# Power_Supply_Circuit_Manual.net
KiCad netlist of a schematic drawn in EAGLE
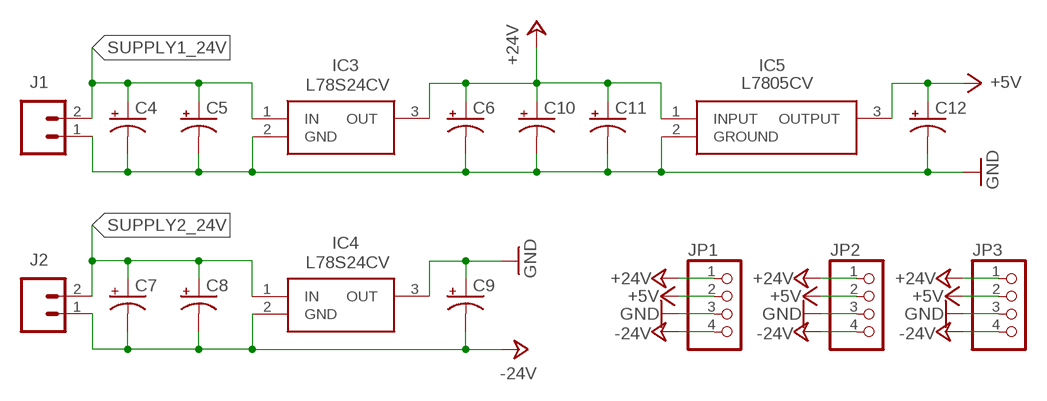
[diagram p0: schematic, sheet 1]

(export (version "E")
  (design (tool "Eeschema 10.0.6"))
  (components
    (comp (ref "C4")
      (value "CPOL-USE2.5-7")
      (footprint "eagle-import:E2,5-7")
      (libsource (lib "eagle-import") (part "CPOL-USE2.5-7"))
    )
    (comp (ref "C5")
      (value "CPOL-USE2.5-7")
      (footprint "eagle-import:E2,5-7")
      (libsource (lib "eagle-import") (part "CPOL-USE2.5-7"))
    )
    (comp (ref "C6")
      (value "CPOL-USE2.5-5")
      (footprint "eagle-import:E2,5-5")
      (libsource (lib "eagle-import") (part "CPOL-USE2.5-5"))
    )
    (comp (ref "C7")
      (value "CPOL-USE2.5-7")
      (footprint "eagle-import:E2,5-7")
      (libsource (lib "eagle-import") (part "CPOL-USE2.5-7"))
    )
    (comp (ref "C8")
      (value "CPOL-USE2.5-7")
      (footprint "eagle-import:E2,5-7")
      (libsource (lib "eagle-import") (part "CPOL-USE2.5-7"))
    )
    (comp (ref "C9")
      (value "CPOL-USE2.5-5")
      (footprint "eagle-import:E2,5-5")
      (libsource (lib "eagle-import") (part "CPOL-USE2.5-5"))
    )
    (comp (ref "C10")
      (value "CPOL-USE2.5-7")
      (footprint "eagle-import:E2,5-7")
      (libsource (lib "eagle-import") (part "CPOL-USE2.5-7"))
    )
    (comp (ref "C11")
      (value "CPOL-USE2.5-7")
      (footprint "eagle-import:E2,5-7")
      (libsource (lib "eagle-import") (part "CPOL-USE2.5-7"))
    )
    (comp (ref "C12")
      (value "CPOL-USE2.5-5")
      (footprint "eagle-import:E2,5-5")
      (libsource (lib "eagle-import") (part "CPOL-USE2.5-5"))
    )
    (comp (ref "IC3")
      (value "L78S24CV")
      (footprint "eagle-import:TO270P460X1020X2008-3P")
      (fields (field (name "MOUSER_PART_NUMBER") "511-L78S24CV"))
      (libsource (lib "eagle-import") (part "L78S24CV"))
    )
    (comp (ref "IC4")
      (value "L78S24CV")
      (footprint "eagle-import:TO270P460X1020X2008-3P")
      (fields (field (name "MOUSER_PART_NUMBER") "511-L78S24CV"))
      (libsource (lib "eagle-import") (part "L78S24CV"))
    )
    (comp (ref "IC5")
      (value "L7805CV")
      (footprint "eagle-import:TO270P460X1020X2008-3P")
      (fields (field (name "MOUSER_PART_NUMBER") "511-L7805CV"))
      (libsource (lib "eagle-import") (part "L7805CV"))
    )
    (comp (ref "J1")
      (value "CONN_025MM")
      (footprint "eagle-import:SCREWTERMINAL-5MM-2")
      (libsource (lib "eagle-import") (part "CONN_025MM"))
    )
    (comp (ref "J2")
      (value "CONN_025MM")
      (footprint "eagle-import:SCREWTERMINAL-5MM-2")
      (libsource (lib "eagle-import") (part "CONN_025MM"))
    )
    (comp (ref "JP1")
      (value "PINHD-1X4")
      (footprint "eagle-import:1X04")
      (libsource (lib "eagle-import") (part "PINHD-1X4"))
    )
    (comp (ref "JP2")
      (value "PINHD-1X4")
      (footprint "eagle-import:1X04")
      (libsource (lib "eagle-import") (part "PINHD-1X4"))
    )
    (comp (ref "JP3")
      (value "PINHD-1X4")
      (footprint "eagle-import:1X04")
      (libsource (lib "eagle-import") (part "PINHD-1X4"))
    )
  )
  (nets
    (net (code "1") (name "+5V") (class "Default")
      (node (ref "C12") (pin "+") (pinfunction "+_+") (pintype "passive"))
      (node (ref "IC5") (pin "3") (pinfunction "OUTPUT_3") (pintype "power_in"))
      (node (ref "JP1") (pin "2") (pinfunction "2_2") (pintype "passive"))
      (node (ref "JP2") (pin "2") (pinfunction "2_2") (pintype "passive"))
      (node (ref "JP3") (pin "2") (pinfunction "2_2") (pintype "passive"))
    )
    (net (code "2") (name "+24V") (class "Default")
      (node (ref "C10") (pin "+") (pinfunction "+_+") (pintype "passive"))
      (node (ref "C11") (pin "+") (pinfunction "+_+") (pintype "passive"))
      (node (ref "C6") (pin "+") (pinfunction "+_+") (pintype "passive"))
      (node (ref "IC3") (pin "3") (pinfunction "OUT_3") (pintype "power_in"))
      (node (ref "IC5") (pin "1") (pinfunction "INPUT_1") (pintype "power_in"))
      (node (ref "JP1") (pin "1") (pinfunction "1_1") (pintype "passive"))
      (node (ref "JP2") (pin "1") (pinfunction "1_1") (pintype "passive"))
      (node (ref "JP3") (pin "1") (pinfunction "1_1") (pintype "passive"))
    )
    (net (code "3") (name "-24V") (class "Default")
      (node (ref "C7") (pin "-") (pinfunction "-_-") (pintype "passive"))
      (node (ref "C8") (pin "-") (pinfunction "-_-") (pintype "passive"))
      (node (ref "C9") (pin "-") (pinfunction "-_-") (pintype "passive"))
      (node (ref "IC4") (pin "2") (pinfunction "GND_2") (pintype "power_in"))
      (node (ref "J2") (pin "1") (pinfunction "1_1") (pintype "passive"))
      (node (ref "JP1") (pin "4") (pinfunction "4_4") (pintype "passive"))
      (node (ref "JP2") (pin "4") (pinfunction "4_4") (pintype "passive"))
      (node (ref "JP3") (pin "4") (pinfunction "4_4") (pintype "passive"))
    )
    (net (code "4") (name "GND") (class "Default")
      (node (ref "C10") (pin "-") (pinfunction "-_-") (pintype "passive"))
      (node (ref "C11") (pin "-") (pinfunction "-_-") (pintype "passive"))
      (node (ref "C12") (pin "-") (pinfunction "-_-") (pintype "passive"))
      (node (ref "C4") (pin "-") (pinfunction "-_-") (pintype "passive"))
      (node (ref "C5") (pin "-") (pinfunction "-_-") (pintype "passive"))
      (node (ref "C6") (pin "-") (pinfunction "-_-") (pintype "passive"))
      (node (ref "C9") (pin "+") (pinfunction "+_+") (pintype "passive"))
      (node (ref "IC3") (pin "2") (pinfunction "GND_2") (pintype "power_in"))
      (node (ref "IC4") (pin "3") (pinfunction "OUT_3") (pintype "power_in"))
      (node (ref "IC5") (pin "2") (pinfunction "GROUND_2") (pintype "power_in"))
      (node (ref "J1") (pin "1") (pinfunction "1_1") (pintype "passive"))
      (node (ref "JP1") (pin "3") (pinfunction "3_3") (pintype "passive"))
      (node (ref "JP2") (pin "3") (pinfunction "3_3") (pintype "passive"))
      (node (ref "JP3") (pin "3") (pinfunction "3_3") (pintype "passive"))
    )
    (net (code "5") (name "SUPPLY1_24V") (class "Default")
      (node (ref "C4") (pin "+") (pinfunction "+_+") (pintype "passive"))
      (node (ref "C5") (pin "+") (pinfunction "+_+") (pintype "passive"))
      (node (ref "IC3") (pin "1") (pinfunction "IN_1") (pintype "power_in"))
      (node (ref "J1") (pin "2") (pinfunction "2_2") (pintype "passive"))
    )
    (net (code "6") (name "SUPPLY2_24V") (class "Default")
      (node (ref "C7") (pin "+") (pinfunction "+_+") (pintype "passive"))
      (node (ref "C8") (pin "+") (pinfunction "+_+") (pintype "passive"))
      (node (ref "IC4") (pin "1") (pinfunction "IN_1") (pintype "power_in"))
      (node (ref "J2") (pin "2") (pinfunction "2_2") (pintype "passive"))
    )
  )
)
